# layout.net
KiCad netlist of a schematic drawn in EAGLE
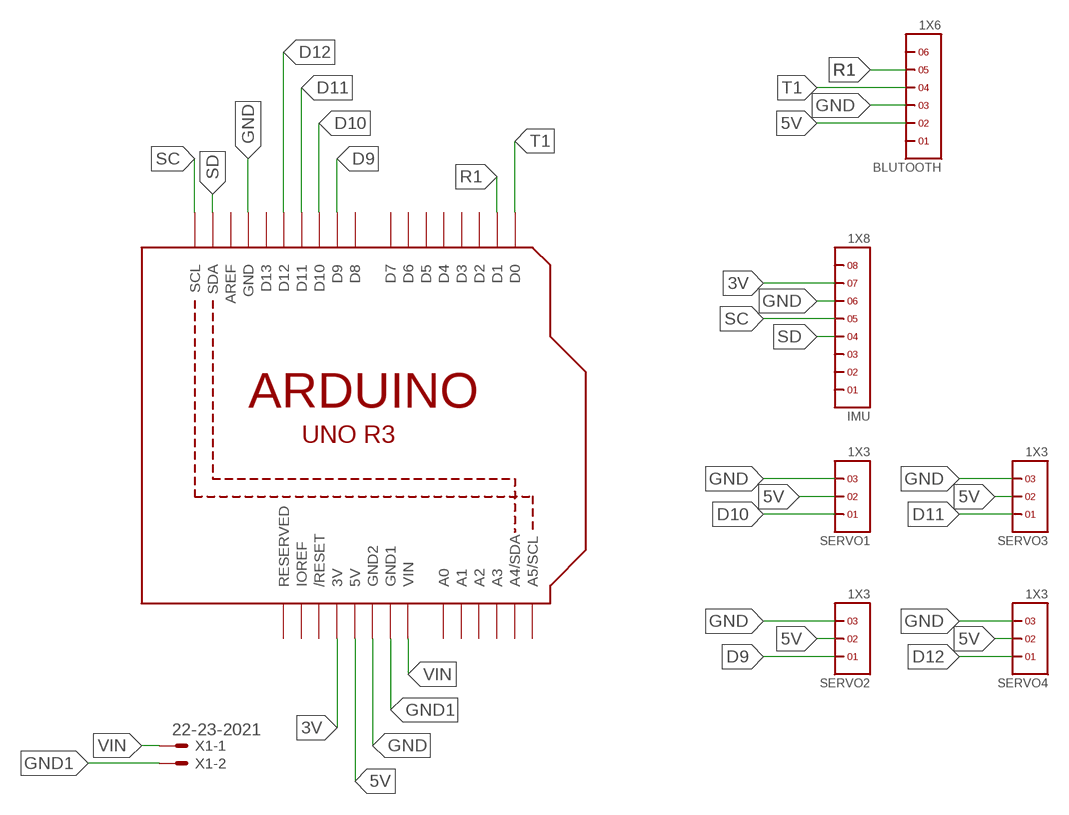
[diagram p0: schematic, sheet 1]

(export (version "E")
  (design (tool "Eeschema 10.0.6"))
  (components
    (comp (ref "BLUTOOTH")
      (value "1X6")
      (footprint "eagle-import:1X6")
      (libsource (lib "eagle-import") (part "1X6"))
    )
    (comp (ref "IMU")
      (value "1X8")
      (footprint "eagle-import:1X8")
      (libsource (lib "eagle-import") (part "1X8"))
    )
    (comp (ref "SERVO1")
      (value "1X3")
      (footprint "eagle-import:1X3")
      (libsource (lib "eagle-import") (part "1X3"))
    )
    (comp (ref "SERVO2")
      (value "1X3")
      (footprint "eagle-import:1X3")
      (libsource (lib "eagle-import") (part "1X3"))
    )
    (comp (ref "SERVO3")
      (value "1X3")
      (footprint "eagle-import:1X3")
      (libsource (lib "eagle-import") (part "1X3"))
    )
    (comp (ref "SERVO4")
      (value "1X3")
      (footprint "eagle-import:1X3")
      (libsource (lib "eagle-import") (part "1X3"))
    )
    (comp (ref "U1")
      (value "ARDUINOR3-DIMENSION")
      (footprint "eagle-import:ARDUINOR3")
      (libsource (lib "eagle-import") (part "ARDUINOR3-DIMENSION"))
    )
    (comp (ref "X1")
      (value "22-23-2021")
      (footprint "eagle-import:22-23-2021")
      (fields (field (name "MF") "MOLEX"))
      (libsource (lib "eagle-import") (part "22-23-2021"))
    )
  )
  (nets
    (net (code "1") (name "3V") (class "Default")
      (node (ref "IMU") (pin "7") (pinfunction "7_7") (pintype "bidirectional"))
      (node (ref "U1") (pin "3V") (pinfunction "3V_3V") (pintype "power_in"))
    )
    (net (code "2") (name "5V") (class "Default")
      (node (ref "BLUTOOTH") (pin "2") (pinfunction "2_2") (pintype "bidirectional"))
      (node (ref "SERVO1") (pin "2") (pinfunction "2_2") (pintype "bidirectional"))
      (node (ref "SERVO2") (pin "2") (pinfunction "2_2") (pintype "bidirectional"))
      (node (ref "SERVO3") (pin "2") (pinfunction "2_2") (pintype "bidirectional"))
      (node (ref "SERVO4") (pin "2") (pinfunction "2_2") (pintype "bidirectional"))
      (node (ref "U1") (pin "5V") (pinfunction "5V_5V") (pintype "power_in"))
    )
    (net (code "3") (name "D9") (class "Default")
      (node (ref "SERVO2") (pin "1") (pinfunction "1_1") (pintype "bidirectional"))
      (node (ref "U1") (pin "D9") (pinfunction "D9_D9") (pintype "bidirectional"))
    )
    (net (code "4") (name "D10") (class "Default")
      (node (ref "SERVO1") (pin "1") (pinfunction "1_1") (pintype "bidirectional"))
      (node (ref "U1") (pin "D10") (pinfunction "D10_D10") (pintype "bidirectional"))
    )
    (net (code "5") (name "D11") (class "Default")
      (node (ref "SERVO3") (pin "1") (pinfunction "1_1") (pintype "bidirectional"))
      (node (ref "U1") (pin "D11") (pinfunction "D11_D11") (pintype "bidirectional"))
    )
    (net (code "6") (name "D12") (class "Default")
      (node (ref "SERVO4") (pin "1") (pinfunction "1_1") (pintype "bidirectional"))
      (node (ref "U1") (pin "D12") (pinfunction "D12_D12") (pintype "bidirectional"))
    )
    (net (code "7") (name "GND") (class "Default")
      (node (ref "BLUTOOTH") (pin "3") (pinfunction "3_3") (pintype "bidirectional"))
      (node (ref "IMU") (pin "6") (pinfunction "6_6") (pintype "bidirectional"))
      (node (ref "SERVO1") (pin "3") (pinfunction "3_3") (pintype "bidirectional"))
      (node (ref "SERVO2") (pin "3") (pinfunction "3_3") (pintype "bidirectional"))
      (node (ref "SERVO3") (pin "3") (pinfunction "3_3") (pintype "bidirectional"))
      (node (ref "SERVO4") (pin "3") (pinfunction "3_3") (pintype "bidirectional"))
      (node (ref "U1") (pin "GND") (pinfunction "GND_GND") (pintype "power_in"))
      (node (ref "U1") (pin "GND2") (pinfunction "GND2_GND2") (pintype "power_in"))
    )
    (net (code "8") (name "GND1") (class "Default")
      (node (ref "U1") (pin "GND1") (pinfunction "GND1_GND1") (pintype "power_in"))
      (node (ref "X1") (pin "2") (pinfunction "S_2") (pintype "passive"))
    )
    (net (code "9") (name "R1") (class "Default")
      (node (ref "BLUTOOTH") (pin "5") (pinfunction "5_5") (pintype "bidirectional"))
      (node (ref "U1") (pin "D1") (pinfunction "D1_D1") (pintype "bidirectional"))
    )
    (net (code "10") (name "SC") (class "Default")
      (node (ref "IMU") (pin "5") (pinfunction "5_5") (pintype "bidirectional"))
      (node (ref "U1") (pin "SCL") (pinfunction "SCL_SCL") (pintype "bidirectional"))
    )
    (net (code "11") (name "SD") (class "Default")
      (node (ref "IMU") (pin "4") (pinfunction "4_4") (pintype "bidirectional"))
      (node (ref "U1") (pin "SDA") (pinfunction "SDA_SDA") (pintype "bidirectional"))
    )
    (net (code "12") (name "T1") (class "Default")
      (node (ref "BLUTOOTH") (pin "4") (pinfunction "4_4") (pintype "bidirectional"))
      (node (ref "U1") (pin "D0") (pinfunction "D0_D0") (pintype "bidirectional"))
    )
    (net (code "13") (name "VIN") (class "Default")
      (node (ref "U1") (pin "VIN") (pinfunction "VIN_VIN") (pintype "power_in"))
      (node (ref "X1") (pin "1") (pinfunction "S_1") (pintype "passive"))
    )
    (net (code "14") (name "unconnected-(BLUTOOTH-Pad1)") (class "Default")
      (node (ref "BLUTOOTH") (pin "1") (pinfunction "1_1") (pintype "bidirectional"))
    )
    (net (code "15") (name "unconnected-(BLUTOOTH-Pad6)") (class "Default")
      (node (ref "BLUTOOTH") (pin "6") (pinfunction "6_6") (pintype "bidirectional"))
    )
    (net (code "16") (name "unconnected-(IMU-Pad1)") (class "Default")
      (node (ref "IMU") (pin "1") (pinfunction "1_1") (pintype "bidirectional"))
    )
    (net (code "17") (name "unconnected-(IMU-Pad2)") (class "Default")
      (node (ref "IMU") (pin "2") (pinfunction "2_2") (pintype "bidirectional"))
    )
    (net (code "18") (name "unconnected-(IMU-Pad3)") (class "Default")
      (node (ref "IMU") (pin "3") (pinfunction "3_3") (pintype "bidirectional"))
    )
    (net (code "19") (name "unconnected-(IMU-Pad8)") (class "Default")
      (node (ref "IMU") (pin "8") (pinfunction "8_8") (pintype "bidirectional"))
    )
    (net (code "20") (name "unconnected-(U1-A4{slash}SDA-PadA4)") (class "Default")
      (node (ref "U1") (pin "A4") (pinfunction "A4/SDA_A4") (pintype "bidirectional"))
    )
    (net (code "21") (name "unconnected-(U1-A5{slash}SCL-PadA5)") (class "Default")
      (node (ref "U1") (pin "A5") (pinfunction "A5/SCL_A5") (pintype "bidirectional"))
    )
    (net (code "22") (name "unconnected-(U1-PadA0)") (class "Default")
      (node (ref "U1") (pin "A0") (pinfunction "A0_A0") (pintype "bidirectional"))
    )
    (net (code "23") (name "unconnected-(U1-PadA1)") (class "Default")
      (node (ref "U1") (pin "A1") (pinfunction "A1_A1") (pintype "bidirectional"))
    )
    (net (code "24") (name "unconnected-(U1-PadA2)") (class "Default")
      (node (ref "U1") (pin "A2") (pinfunction "A2_A2") (pintype "bidirectional"))
    )
    (net (code "25") (name "unconnected-(U1-PadA3)") (class "Default")
      (node (ref "U1") (pin "A3") (pinfunction "A3_A3") (pintype "bidirectional"))
    )
    (net (code "26") (name "unconnected-(U1-PadAREF)") (class "Default")
      (node (ref "U1") (pin "AREF") (pinfunction "AREF_AREF") (pintype "bidirectional"))
    )
    (net (code "27") (name "unconnected-(U1-PadD2)") (class "Default")
      (node (ref "U1") (pin "D2") (pinfunction "D2_D2") (pintype "bidirectional"))
    )
    (net (code "28") (name "unconnected-(U1-PadD3)") (class "Default")
      (node (ref "U1") (pin "D3") (pinfunction "D3_D3") (pintype "bidirectional"))
    )
    (net (code "29") (name "unconnected-(U1-PadD4)") (class "Default")
      (node (ref "U1") (pin "D4") (pinfunction "D4_D4") (pintype "bidirectional"))
    )
    (net (code "30") (name "unconnected-(U1-PadD5)") (class "Default")
      (node (ref "U1") (pin "D5") (pinfunction "D5_D5") (pintype "bidirectional"))
    )
    (net (code "31") (name "unconnected-(U1-PadD6)") (class "Default")
      (node (ref "U1") (pin "D6") (pinfunction "D6_D6") (pintype "bidirectional"))
    )
    (net (code "32") (name "unconnected-(U1-PadD7)") (class "Default")
      (node (ref "U1") (pin "D7") (pinfunction "D7_D7") (pintype "bidirectional"))
    )
    (net (code "33") (name "unconnected-(U1-PadD8)") (class "Default")
      (node (ref "U1") (pin "D8") (pinfunction "D8_D8") (pintype "bidirectional"))
    )
    (net (code "34") (name "unconnected-(U1-PadD13)") (class "Default")
      (node (ref "U1") (pin "D13") (pinfunction "D13_D13") (pintype "bidirectional"))
    )
    (net (code "35") (name "unconnected-(U1-PadIOREF)") (class "Default")
      (node (ref "U1") (pin "IOREF") (pinfunction "IOREF_IOREF") (pintype "output"))
    )
    (net (code "36") (name "unconnected-(U1-PadRESERVED)") (class "Default")
      (node (ref "U1") (pin "RESERVED") (pinfunction "RESERVED_RESERVED") (pintype "no_connect"))
    )
    (net (code "37") (name "unconnected-(U1-{slash}RESET-PadRESET)") (class "Default")
      (node (ref "U1") (pin "RESET") (pinfunction "/RESET_RESET") (pintype "bidirectional"))
    )
  )
)
